# EasyEDA_export.net
KiCad netlist of a schematic drawn in EasyEDA
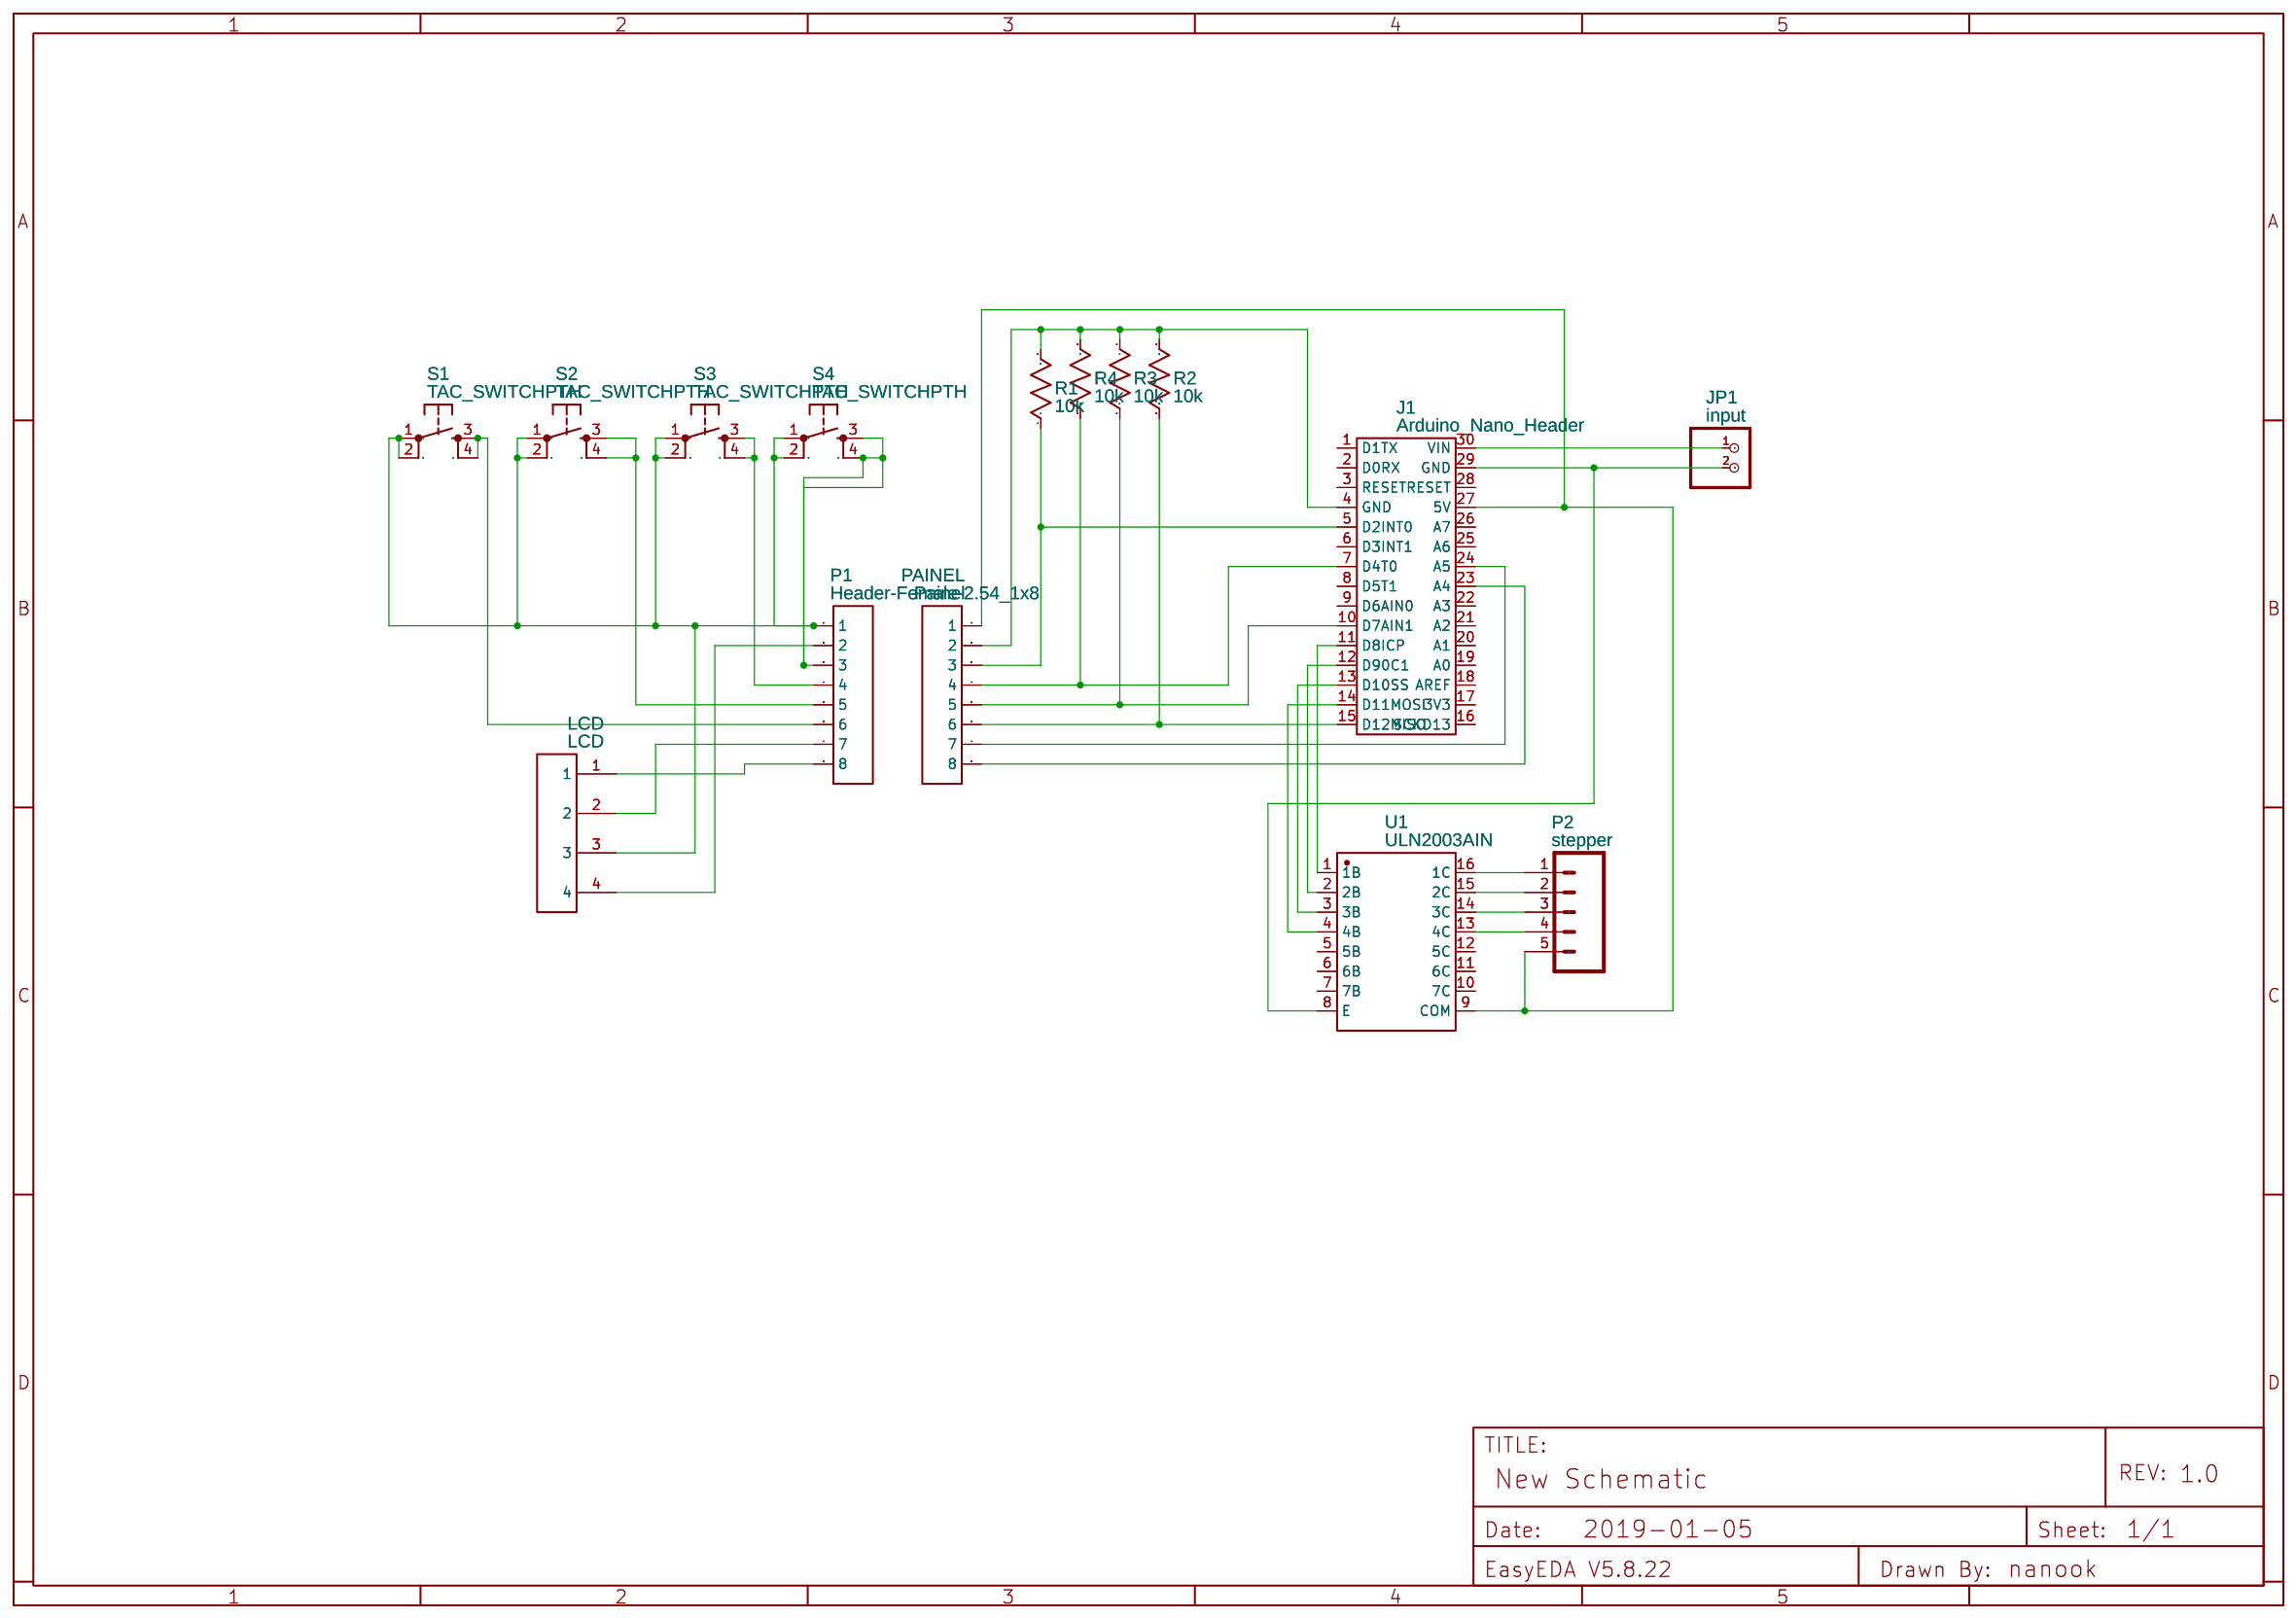
[diagram p0: schematic sheet]

(export (version "E")
  (design (tool "Eeschema 10.0.6"))
  (components
    (comp (ref "J1")
      (value "Arduino_Nano_Header")
      (fields (field (name "BOM_Manufacturer Part") "?"))
      (libsource (lib "") (part "Unknown_705_290"))
    )
    (comp (ref "JP1")
      (value "input")
      (fields (field (name "BOM_Manufacturer Part") "?"))
      (libsource (lib "") (part "Unknown_865_225"))
    )
    (comp (ref "LCD")
      (value "LCD")
      (fields (field (name "BOM_Manufacturer Part") "?") (field (name "BOM_Supplier Part") "undefined"))
      (libsource (lib "") (part "Unknown_305_425"))
    )
    (comp (ref "P1")
      (value "Header-Female-2.54_1x8")
      (fields
        (field (name "BOM_Manufacturer Part") "Female headerHDR1X8-2.54")
        (field (name "BOM_Supplier Part") "C27438")
      )
      (libsource (lib "") (part "Unknown_420_345"))
    )
    (comp (ref "P2")
      (value "stepper")
      (fields (field (name "BOM_Manufacturer Part") "?") (field (name "BOM_Supplier Part") "455-2270-ND"))
      (libsource (lib "") (part "Unknown_805_425"))
    )
    (comp (ref "PAINEL")
      (value "Painel")
      (fields
        (field (name "BOM_Manufacturer Part") "Female headerHDR1X8-2.54")
        (field (name "BOM_Supplier Part") "C27438")
      )
      (libsource (lib "") (part "Unknown_475_345"))
    )
    (comp (ref "R1")
      (value "10k")
      (fields (field (name "BOM_Manufacturer Part") "?"))
      (libsource (lib "") (part "Res_AXIAL-0.3(1/8W)_US_1"))
    )
    (comp (ref "R2")
      (value "10k")
      (fields (field (name "BOM_Manufacturer Part") "?"))
      (libsource (lib "") (part "Res_AXIAL-0.3(1/8W)_US"))
    )
    (comp (ref "R3")
      (value "10k")
      (fields (field (name "BOM_Manufacturer Part") "?"))
      (libsource (lib "") (part "Res_AXIAL-0.3(1/8W)_US"))
    )
    (comp (ref "R4")
      (value "10k")
      (fields (field (name "BOM_Manufacturer Part") "?"))
      (libsource (lib "") (part "Res_AXIAL-0.3(1/8W)_US"))
    )
    (comp (ref "S1")
      (value "TAC_SWITCHPTH")
      (fields (field (name "BOM_Manufacturer Part") "?"))
      (libsource (lib "") (part "Unknown_215_215"))
    )
    (comp (ref "S2")
      (value "TAC_SWITCHPTH")
      (fields (field (name "BOM_Manufacturer Part") "?"))
      (libsource (lib "") (part "Unknown_280_215"))
    )
    (comp (ref "S3")
      (value "TAC_SWITCHPTH")
      (fields (field (name "BOM_Manufacturer Part") "?"))
      (libsource (lib "") (part "Unknown_350_215"))
    )
    (comp (ref "S4")
      (value "TAC_SWITCHPTH")
      (fields (field (name "BOM_Manufacturer Part") "?"))
      (libsource (lib "") (part "Unknown_410_215"))
    )
    (comp (ref "U1")
      (value "ULN2003AIN")
      (fields (field (name "BOM_Supplier Part") "C90838"))
      (libsource (lib "") (part "Unknown_700_465"))
    )
  )
  (nets
    (net (code "1") (name "Net-(J1-5V)") (class "Default")
      (node (ref "J1") (pin "27") (pinfunction "5V_27") (pintype "unspecified"))
      (node (ref "P2") (pin "5") (pinfunction "5_5") (pintype "unspecified"))
      (node (ref "PAINEL") (pin "1") (pinfunction "1_1") (pintype "input"))
      (node (ref "U1") (pin "9") (pinfunction "COM_9") (pintype "unspecified"))
    )
    (net (code "2") (name "Net-(J1-A4)") (class "Default")
      (node (ref "J1") (pin "23") (pinfunction "A4_23") (pintype "unspecified"))
      (node (ref "PAINEL") (pin "8") (pinfunction "8_8") (pintype "input"))
    )
    (net (code "3") (name "Net-(J1-A5)") (class "Default")
      (node (ref "J1") (pin "24") (pinfunction "A5_24") (pintype "unspecified"))
      (node (ref "PAINEL") (pin "7") (pinfunction "7_7") (pintype "input"))
    )
    (net (code "4") (name "Net-(J1-D2INT0)") (class "Default")
      (node (ref "J1") (pin "5") (pinfunction "D2INT0_5") (pintype "unspecified"))
      (node (ref "PAINEL") (pin "3") (pinfunction "3_3") (pintype "input"))
      (node (ref "R1") (pin "1") (pinfunction "1_1") (pintype "unspecified"))
    )
    (net (code "5") (name "Net-(J1-D4T0)") (class "Default")
      (node (ref "J1") (pin "7") (pinfunction "D4T0_7") (pintype "unspecified"))
      (node (ref "PAINEL") (pin "4") (pinfunction "4_4") (pintype "input"))
      (node (ref "R4") (pin "2") (pinfunction "2_2") (pintype "unspecified"))
    )
    (net (code "6") (name "Net-(J1-D7AIN1)") (class "Default")
      (node (ref "J1") (pin "10") (pinfunction "D7AIN1_10") (pintype "unspecified"))
      (node (ref "PAINEL") (pin "5") (pinfunction "5_5") (pintype "input"))
      (node (ref "R3") (pin "2") (pinfunction "2_2") (pintype "unspecified"))
    )
    (net (code "7") (name "Net-(J1-D8ICP)") (class "Default")
      (node (ref "J1") (pin "11") (pinfunction "D8ICP_11") (pintype "unspecified"))
      (node (ref "U1") (pin "1") (pinfunction "1B_1") (pintype "unspecified"))
    )
    (net (code "8") (name "Net-(J1-D10SS)") (class "Default")
      (node (ref "J1") (pin "13") (pinfunction "D10SS_13") (pintype "unspecified"))
      (node (ref "U1") (pin "3") (pinfunction "3B_3") (pintype "unspecified"))
    )
    (net (code "9") (name "Net-(J1-D11MOSI)") (class "Default")
      (node (ref "J1") (pin "14") (pinfunction "D11MOSI_14") (pintype "unspecified"))
      (node (ref "U1") (pin "4") (pinfunction "4B_4") (pintype "unspecified"))
    )
    (net (code "10") (name "Net-(J1-D12MISO)") (class "Default")
      (node (ref "J1") (pin "15") (pinfunction "D12MISO_15") (pintype "unspecified"))
      (node (ref "PAINEL") (pin "6") (pinfunction "6_6") (pintype "input"))
      (node (ref "R2") (pin "2") (pinfunction "2_2") (pintype "unspecified"))
    )
    (net (code "11") (name "Net-(J1-D90C1)") (class "Default")
      (node (ref "J1") (pin "12") (pinfunction "D90C1_12") (pintype "unspecified"))
      (node (ref "U1") (pin "2") (pinfunction "2B_2") (pintype "unspecified"))
    )
    (net (code "12") (name "Net-(J1-GND-Pad4)") (class "Default")
      (node (ref "J1") (pin "4") (pinfunction "GND_4") (pintype "unspecified"))
      (node (ref "PAINEL") (pin "2") (pinfunction "2_2") (pintype "input"))
      (node (ref "R1") (pin "2") (pinfunction "2_2") (pintype "unspecified"))
      (node (ref "R2") (pin "1") (pinfunction "1_1") (pintype "unspecified"))
      (node (ref "R3") (pin "1") (pinfunction "1_1") (pintype "unspecified"))
      (node (ref "R4") (pin "1") (pinfunction "1_1") (pintype "unspecified"))
    )
    (net (code "13") (name "Net-(J1-VIN)") (class "Default")
      (node (ref "J1") (pin "30") (pinfunction "VIN_30") (pintype "unspecified"))
      (node (ref "JP1") (pin "1") (pinfunction "1_1") (pintype "bidirectional"))
    )
    (net (code "14") (name "Net-(LCD-Pad1)") (class "Default")
      (node (ref "LCD") (pin "1") (pinfunction "1_1") (pintype "unspecified"))
      (node (ref "P1") (pin "8") (pinfunction "8_8") (pintype "input"))
    )
    (net (code "15") (name "Net-(LCD-Pad2)") (class "Default")
      (node (ref "LCD") (pin "2") (pinfunction "2_2") (pintype "unspecified"))
      (node (ref "P1") (pin "7") (pinfunction "7_7") (pintype "input"))
    )
    (net (code "16") (name "Net-(LCD-Pad3)") (class "Default")
      (node (ref "LCD") (pin "3") (pinfunction "3_3") (pintype "unspecified"))
      (node (ref "P1") (pin "1") (pinfunction "1_1") (pintype "input"))
      (node (ref "S1") (pin "1") (pinfunction "1_1") (pintype "unspecified"))
      (node (ref "S1") (pin "2") (pinfunction "2_2") (pintype "unspecified"))
      (node (ref "S2") (pin "1") (pinfunction "1_1") (pintype "unspecified"))
      (node (ref "S2") (pin "2") (pinfunction "2_2") (pintype "unspecified"))
      (node (ref "S3") (pin "1") (pinfunction "1_1") (pintype "unspecified"))
      (node (ref "S3") (pin "2") (pinfunction "2_2") (pintype "unspecified"))
      (node (ref "S4") (pin "1") (pinfunction "1_1") (pintype "unspecified"))
      (node (ref "S4") (pin "2") (pinfunction "2_2") (pintype "unspecified"))
    )
    (net (code "17") (name "Net-(LCD-Pad4)") (class "Default")
      (node (ref "LCD") (pin "4") (pinfunction "4_4") (pintype "unspecified"))
      (node (ref "P1") (pin "2") (pinfunction "2_2") (pintype "input"))
    )
    (net (code "18") (name "Net-(P1-Pad3)") (class "Default")
      (node (ref "P1") (pin "3") (pinfunction "3_3") (pintype "input"))
      (node (ref "S4") (pin "3") (pinfunction "3_3") (pintype "unspecified"))
      (node (ref "S4") (pin "4") (pinfunction "4_4") (pintype "unspecified"))
    )
    (net (code "19") (name "Net-(P1-Pad4)") (class "Default")
      (node (ref "P1") (pin "4") (pinfunction "4_4") (pintype "input"))
      (node (ref "S3") (pin "3") (pinfunction "3_3") (pintype "unspecified"))
      (node (ref "S3") (pin "4") (pinfunction "4_4") (pintype "unspecified"))
    )
    (net (code "20") (name "Net-(P1-Pad5)") (class "Default")
      (node (ref "P1") (pin "5") (pinfunction "5_5") (pintype "input"))
      (node (ref "S2") (pin "3") (pinfunction "3_3") (pintype "unspecified"))
      (node (ref "S2") (pin "4") (pinfunction "4_4") (pintype "unspecified"))
    )
    (net (code "21") (name "Net-(P1-Pad6)") (class "Default")
      (node (ref "P1") (pin "6") (pinfunction "6_6") (pintype "input"))
      (node (ref "S1") (pin "3") (pinfunction "3_3") (pintype "unspecified"))
      (node (ref "S1") (pin "4") (pinfunction "4_4") (pintype "unspecified"))
    )
    (net (code "22") (name "Net-(U1-1C)") (class "Default")
      (node (ref "P2") (pin "1") (pinfunction "1_1") (pintype "unspecified"))
      (node (ref "U1") (pin "16") (pinfunction "1C_16") (pintype "unspecified"))
    )
    (net (code "23") (name "Net-(U1-2C)") (class "Default")
      (node (ref "P2") (pin "2") (pinfunction "2_2") (pintype "unspecified"))
      (node (ref "U1") (pin "15") (pinfunction "2C_15") (pintype "unspecified"))
    )
    (net (code "24") (name "Net-(U1-3C)") (class "Default")
      (node (ref "P2") (pin "3") (pinfunction "3_3") (pintype "unspecified"))
      (node (ref "U1") (pin "14") (pinfunction "3C_14") (pintype "unspecified"))
    )
    (net (code "25") (name "Net-(U1-4C)") (class "Default")
      (node (ref "P2") (pin "4") (pinfunction "4_4") (pintype "unspecified"))
      (node (ref "U1") (pin "13") (pinfunction "4C_13") (pintype "unspecified"))
    )
    (net (code "26") (name "Net-(U1-E)") (class "Default")
      (node (ref "J1") (pin "29") (pinfunction "GND_29") (pintype "unspecified"))
      (node (ref "JP1") (pin "2") (pinfunction "2_2") (pintype "bidirectional"))
      (node (ref "U1") (pin "8") (pinfunction "E_8") (pintype "unspecified"))
    )
    (net (code "27") (name "unconnected-(J1-3V3-Pad17)") (class "Default")
      (node (ref "J1") (pin "17") (pinfunction "3V3_17") (pintype "unspecified"))
    )
    (net (code "28") (name "unconnected-(J1-A0-Pad19)") (class "Default")
      (node (ref "J1") (pin "19") (pinfunction "A0_19") (pintype "unspecified"))
    )
    (net (code "29") (name "unconnected-(J1-A1-Pad20)") (class "Default")
      (node (ref "J1") (pin "20") (pinfunction "A1_20") (pintype "unspecified"))
    )
    (net (code "30") (name "unconnected-(J1-A2-Pad21)") (class "Default")
      (node (ref "J1") (pin "21") (pinfunction "A2_21") (pintype "unspecified"))
    )
    (net (code "31") (name "unconnected-(J1-A3-Pad22)") (class "Default")
      (node (ref "J1") (pin "22") (pinfunction "A3_22") (pintype "unspecified"))
    )
    (net (code "32") (name "unconnected-(J1-A6-Pad25)") (class "Default")
      (node (ref "J1") (pin "25") (pinfunction "A6_25") (pintype "unspecified"))
    )
    (net (code "33") (name "unconnected-(J1-A7-Pad26)") (class "Default")
      (node (ref "J1") (pin "26") (pinfunction "A7_26") (pintype "unspecified"))
    )
    (net (code "34") (name "unconnected-(J1-AREF-Pad18)") (class "Default")
      (node (ref "J1") (pin "18") (pinfunction "AREF_18") (pintype "unspecified"))
    )
    (net (code "35") (name "unconnected-(J1-D0RX-Pad2)") (class "Default")
      (node (ref "J1") (pin "2") (pinfunction "D0RX_2") (pintype "unspecified"))
    )
    (net (code "36") (name "unconnected-(J1-D1TX-Pad1)") (class "Default")
      (node (ref "J1") (pin "1") (pinfunction "D1TX_1") (pintype "unspecified"))
    )
    (net (code "37") (name "unconnected-(J1-D3INT1-Pad6)") (class "Default")
      (node (ref "J1") (pin "6") (pinfunction "D3INT1_6") (pintype "unspecified"))
    )
    (net (code "38") (name "unconnected-(J1-D5T1-Pad8)") (class "Default")
      (node (ref "J1") (pin "8") (pinfunction "D5T1_8") (pintype "unspecified"))
    )
    (net (code "39") (name "unconnected-(J1-D6AIN0-Pad9)") (class "Default")
      (node (ref "J1") (pin "9") (pinfunction "D6AIN0_9") (pintype "unspecified"))
    )
    (net (code "40") (name "unconnected-(J1-RESET-Pad3)") (class "Default")
      (node (ref "J1") (pin "3") (pinfunction "RESET_3") (pintype "unspecified"))
    )
    (net (code "41") (name "unconnected-(J1-RESET-Pad28)") (class "Default")
      (node (ref "J1") (pin "28") (pinfunction "RESET_28") (pintype "unspecified"))
    )
    (net (code "42") (name "unconnected-(J1-SCKD13-Pad16)") (class "Default")
      (node (ref "J1") (pin "16") (pinfunction "SCKD13_16") (pintype "unspecified"))
    )
    (net (code "43") (name "unconnected-(U1-5B-Pad5)") (class "Default")
      (node (ref "U1") (pin "5") (pinfunction "5B_5") (pintype "unspecified"))
    )
    (net (code "44") (name "unconnected-(U1-5C-Pad12)") (class "Default")
      (node (ref "U1") (pin "12") (pinfunction "5C_12") (pintype "unspecified"))
    )
    (net (code "45") (name "unconnected-(U1-6B-Pad6)") (class "Default")
      (node (ref "U1") (pin "6") (pinfunction "6B_6") (pintype "unspecified"))
    )
    (net (code "46") (name "unconnected-(U1-6C-Pad11)") (class "Default")
      (node (ref "U1") (pin "11") (pinfunction "6C_11") (pintype "unspecified"))
    )
    (net (code "47") (name "unconnected-(U1-7B-Pad7)") (class "Default")
      (node (ref "U1") (pin "7") (pinfunction "7B_7") (pintype "unspecified"))
    )
    (net (code "48") (name "unconnected-(U1-7C-Pad10)") (class "Default")
      (node (ref "U1") (pin "10") (pinfunction "7C_10") (pintype "unspecified"))
    )
  )
)
